# DAPLinkTiny.net
KiCad netlist of a schematic drawn in Altium Designer
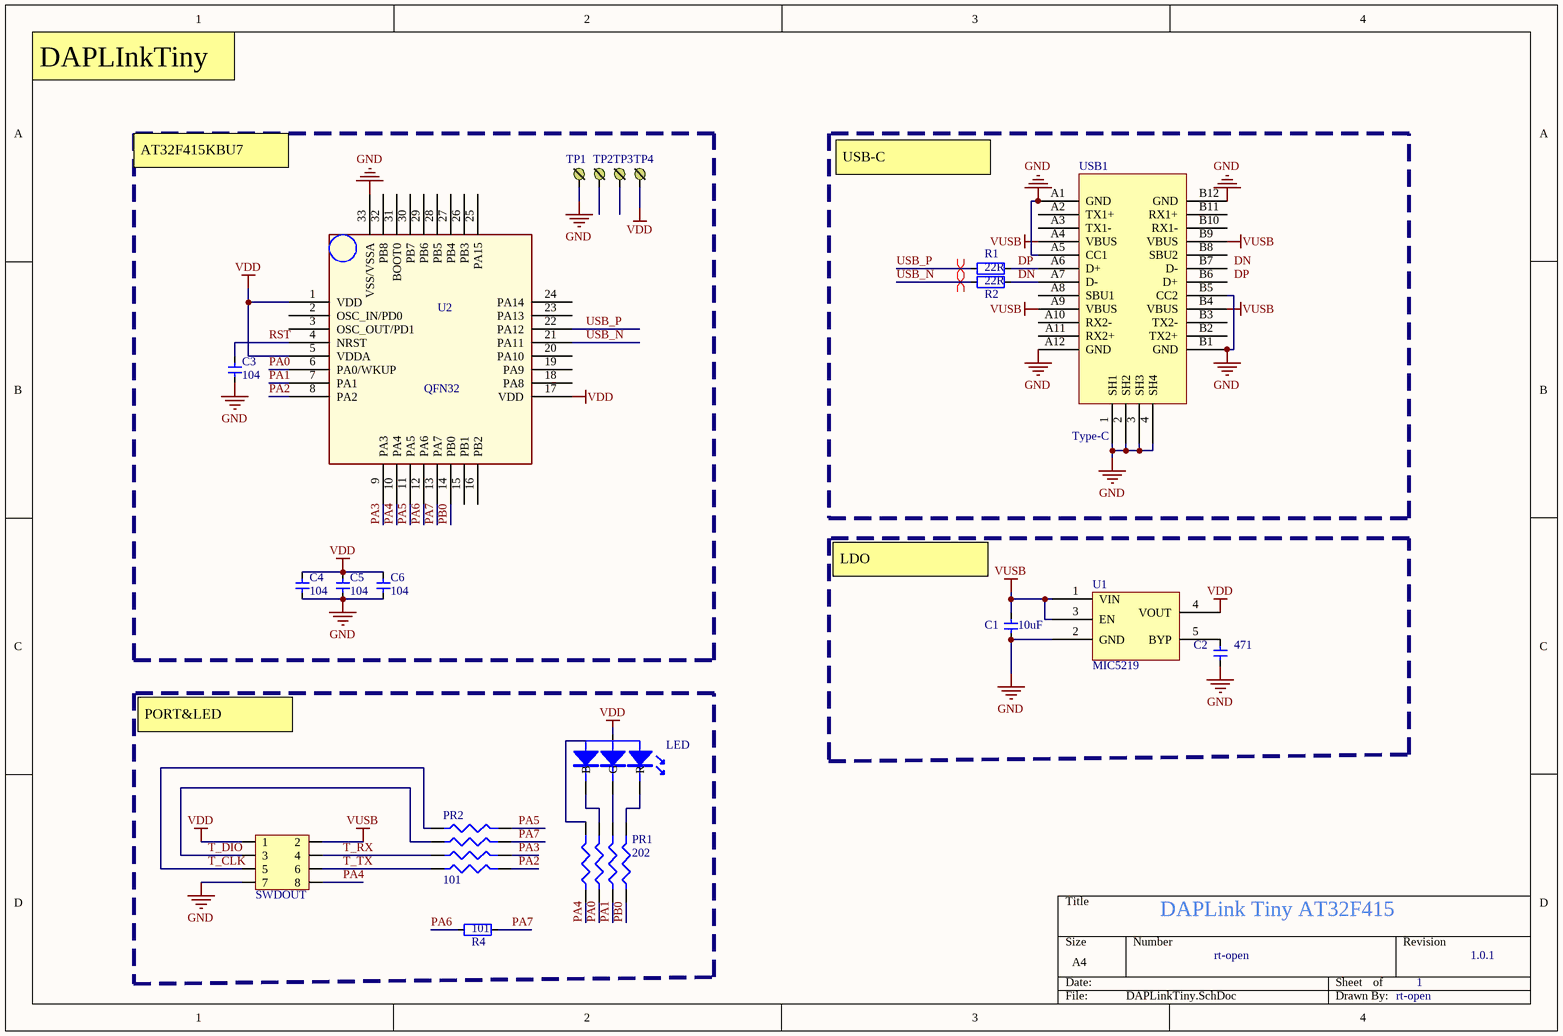
[diagram p0: DAPLinkTiny.SchDoc]

(export (version "E")
  (design (tool "Eeschema 10.0.6"))
  (components
    (comp (ref "C1")
      (value "10uF")
      (footprint "PCB_PassiveCap:CAP_0603")
      (fields (field (name "Comment") "Cap_0603"))
      (libsource (lib "SCH_Passive") (part "Cap_0603"))
    )
    (comp (ref "C2")
      (value "471")
      (footprint "PCB_PassiveCap:CAP_0603")
      (description "Capacitor")
      (fields (field (name "Comment") "Cap_0603"))
      (libsource (lib "SCH_Passive") (part "Cap_0603"))
    )
    (comp (ref "C3")
      (value "104")
      (footprint "PCB_PassiveCap:CAP_0603")
      (description "Capacitor")
      (fields (field (name "Comment") "Cap_0603"))
      (libsource (lib "SCH_Passive") (part "Cap_0603"))
    )
    (comp (ref "C4")
      (value "104")
      (footprint "PCB_PassiveCap:CAP_0603")
      (description "Capacitor")
      (fields (field (name "Comment") "Cap_0603"))
      (libsource (lib "SCH_Passive") (part "Cap_0603"))
    )
    (comp (ref "C5")
      (value "104")
      (footprint "PCB_PassiveCap:CAP_0603")
      (description "Capacitor")
      (fields (field (name "Comment") "Cap_0603"))
      (libsource (lib "SCH_Passive") (part "Cap_0603"))
    )
    (comp (ref "C6")
      (value "104")
      (footprint "PCB_PassiveCap:CAP_0603")
      (description "Capacitor")
      (fields (field (name "Comment") "Cap_0603"))
      (libsource (lib "SCH_Passive") (part "Cap_0603"))
    )
    (comp (ref "LED")
      (value "LTST-C19HE1WT")
      (footprint "LTST-C19HE1WT")
      (libsource (lib "PIXRACER-R12") (part "RGB_LED_5MM"))
    )
    (comp (ref "PR1") (value "202") (footprint "RES4B") (libsource (lib "3DGeneral") (part "RES4B")))
    (comp (ref "PR2") (value "101") (footprint "RES4B") (libsource (lib "3DGeneral") (part "RES4B")))
    (comp (ref "R1")
      (value "22R")
      (footprint "PCB_PassiveRes:RES_0603")
      (description "Resistor")
      (fields (field (name "Comment") "Res_0603"))
      (libsource (lib "SCH_Passive") (part "Res_0603"))
    )
    (comp (ref "R2")
      (value "22R")
      (footprint "PCB_PassiveRes:RES_0603")
      (description "Resistor")
      (fields (field (name "Comment") "Res_0603"))
      (libsource (lib "SCH_Passive") (part "Res_0603"))
    )
    (comp (ref "R4")
      (value "101")
      (footprint "PCB_PassiveRes:RES_0603")
      (description "Resistor")
      (fields (field (name "Comment") "Res_0603"))
      (libsource (lib "SCH_Passive") (part "Res_0603"))
    )
    (comp (ref "SWDOUT")
      (value "HDR2x4_2.54")
      (footprint "PCB_ConnectorHDR:HDR2X4_2.54_180H")
      (description "Header")
      (libsource (lib "SCH_ConnectorHDR") (part "HDR2x4_2.54"))
    )
    (comp (ref "TP1") (value "PLUG") (footprint "SMT_PAD_ROUND") (libsource (lib "AUAV-X1_R1") (part "PLUG")))
    (comp (ref "TP2") (value "PLUG") (footprint "SMT_PAD_ROUND") (libsource (lib "AUAV-X1_R1") (part "PLUG")))
    (comp (ref "TP3") (value "PLUG") (footprint "SMT_PAD_ROUND") (libsource (lib "AUAV-X1_R1") (part "PLUG")))
    (comp (ref "TP4") (value "PLUG") (footprint "SMT_PAD_ROUND") (libsource (lib "AUAV-X1_R1") (part "PLUG")))
    (comp (ref "U1") (value "MIC5219") (footprint "SOT23-5") (libsource (lib "PCB") (part "MIC5219")))
    (comp (ref "U2") (value "QFN32") (libsource (lib "AT32F415-ALL") (part "QFN32")))
    (comp (ref "USB1") (value "Type-C") (footprint "Type-C") (libsource (lib "元件") (part "Type-C")))
  )
  (nets
    (net (code "1") (name "/DN") (class "Default")
      (node (ref "R2") (pin "2") (pinfunction "2_2") (pintype "passive"))
      (node (ref "USB1") (pin "A7") (pinfunction "D-_A7") (pintype "passive"))
    )
    (net (code "2") (name "/DP") (class "Default")
      (node (ref "R1") (pin "2") (pinfunction "2_2") (pintype "passive"))
      (node (ref "USB1") (pin "A6") (pinfunction "D+_A6") (pintype "passive"))
    )
    (net (code "3") (name "/PA0") (class "Default")
      (node (ref "PR1") (pin "3") (pinfunction "R2_3") (pintype "passive"))
      (node (ref "U2") (pin "6") (pinfunction "PA0/WKUP_6") (pintype "passive"))
    )
    (net (code "4") (name "/PA1") (class "Default")
      (node (ref "PR1") (pin "5") (pinfunction "R3_5") (pintype "passive"))
      (node (ref "U2") (pin "7") (pinfunction "PA1_7") (pintype "passive"))
    )
    (net (code "5") (name "/PA2") (class "Default")
      (node (ref "PR2") (pin "8") (pinfunction "R0_8") (pintype "passive"))
      (node (ref "U2") (pin "8") (pinfunction "PA2_8") (pintype "passive"))
    )
    (net (code "6") (name "/PA3") (class "Default")
      (node (ref "PR2") (pin "6") (pinfunction "R2_6") (pintype "passive"))
      (node (ref "U2") (pin "9") (pinfunction "PA3_9") (pintype "passive"))
    )
    (net (code "7") (name "/PA4") (class "Default")
      (node (ref "PR1") (pin "1") (pinfunction "R0_1") (pintype "passive"))
      (node (ref "SWDOUT") (pin "8") (pinfunction "8_8") (pintype "passive"))
      (node (ref "U2") (pin "10") (pinfunction "PA4_10") (pintype "passive"))
    )
    (net (code "8") (name "/PA5") (class "Default")
      (node (ref "PR2") (pin "2") (pinfunction "R1_2") (pintype "passive"))
      (node (ref "U2") (pin "11") (pinfunction "PA5_11") (pintype "passive"))
    )
    (net (code "9") (name "/PA6") (class "Default")
      (node (ref "R4") (pin "1") (pinfunction "1_1") (pintype "passive"))
      (node (ref "U2") (pin "12") (pinfunction "PA6_12") (pintype "passive"))
    )
    (net (code "10") (name "/PA7") (class "Default")
      (node (ref "PR2") (pin "4") (pinfunction "R3_4") (pintype "passive"))
      (node (ref "R4") (pin "2") (pinfunction "2_2") (pintype "passive"))
      (node (ref "U2") (pin "13") (pinfunction "PA7_13") (pintype "passive"))
    )
    (net (code "11") (name "/PB0") (class "Default")
      (node (ref "PR1") (pin "7") (pinfunction "R1_7") (pintype "passive"))
      (node (ref "U2") (pin "14") (pinfunction "PB0_14") (pintype "passive"))
    )
    (net (code "12") (name "/RST") (class "Default")
      (node (ref "C3") (pin "2") (pinfunction "2_2") (pintype "passive"))
      (node (ref "U2") (pin "4") (pinfunction "NRST_4") (pintype "passive"))
    )
    (net (code "13") (name "/T_CLK") (class "Default")
      (node (ref "PR2") (pin "1") (pinfunction "R0_1") (pintype "passive"))
      (node (ref "SWDOUT") (pin "5") (pinfunction "5_5") (pintype "passive"))
    )
    (net (code "14") (name "/T_DIO") (class "Default")
      (node (ref "PR2") (pin "3") (pinfunction "R2_3") (pintype "passive"))
      (node (ref "SWDOUT") (pin "3") (pinfunction "3_3") (pintype "passive"))
    )
    (net (code "15") (name "/T_RX") (class "Default")
      (node (ref "PR2") (pin "5") (pinfunction "R3_5") (pintype "passive"))
      (node (ref "SWDOUT") (pin "4") (pinfunction "4_4") (pintype "passive"))
    )
    (net (code "16") (name "/T_TX") (class "Default")
      (node (ref "PR2") (pin "7") (pinfunction "R1_7") (pintype "passive"))
      (node (ref "SWDOUT") (pin "6") (pinfunction "6_6") (pintype "passive"))
    )
    (net (code "17") (name "/USB_N") (class "Default")
      (node (ref "R2") (pin "1") (pinfunction "1_1") (pintype "passive"))
      (node (ref "U2") (pin "21") (pinfunction "PA11_21") (pintype "passive"))
    )
    (net (code "18") (name "/USB_P") (class "Default")
      (node (ref "R1") (pin "1") (pinfunction "1_1") (pintype "passive"))
      (node (ref "U2") (pin "22") (pinfunction "PA12_22") (pintype "passive"))
    )
    (net (code "19") (name "GND") (class "Default")
      (node (ref "C1") (pin "1") (pinfunction "1_1") (pintype "passive"))
      (node (ref "C2") (pin "1") (pinfunction "1_1") (pintype "passive"))
      (node (ref "C3") (pin "1") (pinfunction "1_1") (pintype "passive"))
      (node (ref "C4") (pin "1") (pinfunction "1_1") (pintype "passive"))
      (node (ref "C5") (pin "1") (pinfunction "1_1") (pintype "passive"))
      (node (ref "C6") (pin "1") (pinfunction "1_1") (pintype "passive"))
      (node (ref "SWDOUT") (pin "7") (pinfunction "7_7") (pintype "passive"))
      (node (ref "TP1") (pin "1") (pintype "passive"))
      (node (ref "U1") (pin "2") (pinfunction "GND_2") (pintype "passive"))
      (node (ref "U2") (pin "33") (pinfunction "VSS/VSSA_33") (pintype "passive"))
      (node (ref "USB1") (pin "1") (pinfunction "SH1_1") (pintype "passive"))
      (node (ref "USB1") (pin "2") (pinfunction "SH2_2") (pintype "passive"))
      (node (ref "USB1") (pin "3") (pinfunction "SH3_3") (pintype "passive"))
      (node (ref "USB1") (pin "4") (pinfunction "SH4_4") (pintype "passive"))
      (node (ref "USB1") (pin "A1") (pinfunction "GND_A1") (pintype "passive"))
      (node (ref "USB1") (pin "A12") (pinfunction "GND_A12") (pintype "passive"))
      (node (ref "USB1") (pin "A5") (pinfunction "CC1_A5") (pintype "passive"))
      (node (ref "USB1") (pin "B1") (pinfunction "GND_B1") (pintype "passive"))
      (node (ref "USB1") (pin "B12") (pinfunction "GND_B12") (pintype "passive"))
      (node (ref "USB1") (pin "B5") (pinfunction "CC2_B5") (pintype "passive"))
    )
    (net (code "20") (name "Net-(LED-B)") (class "Default")
      (node (ref "LED") (pin "3") (pinfunction "B_3") (pintype "passive"))
      (node (ref "PR1") (pin "4") (pinfunction "R3_4") (pintype "passive"))
    )
    (net (code "21") (name "Net-(LED-G)") (class "Default")
      (node (ref "LED") (pin "2") (pinfunction "G_2") (pintype "passive"))
      (node (ref "PR1") (pin "6") (pinfunction "R2_6") (pintype "passive"))
    )
    (net (code "22") (name "Net-(LED-R)") (class "Default")
      (node (ref "LED") (pin "1") (pinfunction "R_1") (pintype "passive"))
      (node (ref "PR1") (pin "8") (pinfunction "R0_8") (pintype "passive"))
    )
    (net (code "23") (name "Net-(U1-BYP)") (class "Default")
      (node (ref "C2") (pin "2") (pinfunction "2_2") (pintype "passive"))
      (node (ref "U1") (pin "5") (pinfunction "BYP_5") (pintype "passive"))
    )
    (net (code "24") (name "VDD") (class "Default")
      (node (ref "C4") (pin "2") (pinfunction "2_2") (pintype "passive"))
      (node (ref "C5") (pin "2") (pinfunction "2_2") (pintype "passive"))
      (node (ref "C6") (pin "2") (pinfunction "2_2") (pintype "passive"))
      (node (ref "LED") (pin "4") (pinfunction "A_4") (pintype "passive"))
      (node (ref "SWDOUT") (pin "1") (pinfunction "1_1") (pintype "passive"))
      (node (ref "TP4") (pin "1") (pintype "passive"))
      (node (ref "U1") (pin "4") (pinfunction "VOUT_4") (pintype "passive"))
      (node (ref "U2") (pin "1") (pinfunction "VDD_1") (pintype "passive"))
      (node (ref "U2") (pin "17") (pinfunction "VDD_17") (pintype "passive"))
      (node (ref "U2") (pin "5") (pinfunction "VDDA_5") (pintype "passive"))
    )
    (net (code "25") (name "VUSB") (class "Default")
      (node (ref "C1") (pin "2") (pinfunction "2_2") (pintype "passive"))
      (node (ref "SWDOUT") (pin "2") (pinfunction "2_2") (pintype "passive"))
      (node (ref "U1") (pin "1") (pinfunction "VIN_1") (pintype "passive"))
      (node (ref "U1") (pin "3") (pinfunction "EN_3") (pintype "passive"))
      (node (ref "USB1") (pin "A4") (pinfunction "VBUS_A4") (pintype "passive"))
      (node (ref "USB1") (pin "A9") (pinfunction "VBUS_A9") (pintype "passive"))
      (node (ref "USB1") (pin "B4") (pinfunction "VBUS_B4") (pintype "passive"))
      (node (ref "USB1") (pin "B9") (pinfunction "VBUS_B9") (pintype "passive"))
    )
    (net (code "26") (name "unconnected-(PR1-R1-Pad2)") (class "Default")
      (node (ref "PR1") (pin "2") (pinfunction "R1_2") (pintype "passive"))
    )
    (net (code "27") (name "unconnected-(TP2-Pad1)") (class "Default")
      (node (ref "TP2") (pin "1") (pintype "passive"))
    )
    (net (code "28") (name "unconnected-(TP3-Pad1)") (class "Default")
      (node (ref "TP3") (pin "1") (pintype "passive"))
    )
    (net (code "29") (name "unconnected-(U2-BOOT0-Pad31)") (class "Default")
      (node (ref "U2") (pin "31") (pinfunction "BOOT0_31") (pintype "passive"))
    )
    (net (code "30") (name "unconnected-(U2-OSC_IN{slash}PD0-Pad2)") (class "Default")
      (node (ref "U2") (pin "2") (pinfunction "OSC_IN/PD0_2") (pintype "passive"))
    )
    (net (code "31") (name "unconnected-(U2-OSC_OUT{slash}PD1-Pad3)") (class "Default")
      (node (ref "U2") (pin "3") (pinfunction "OSC_OUT/PD1_3") (pintype "passive"))
    )
    (net (code "32") (name "unconnected-(U2-PA8-Pad18)") (class "Default")
      (node (ref "U2") (pin "18") (pinfunction "PA8_18") (pintype "passive"))
    )
    (net (code "33") (name "unconnected-(U2-PA9-Pad19)") (class "Default")
      (node (ref "U2") (pin "19") (pinfunction "PA9_19") (pintype "passive"))
    )
    (net (code "34") (name "unconnected-(U2-PA10-Pad20)") (class "Default")
      (node (ref "U2") (pin "20") (pinfunction "PA10_20") (pintype "passive"))
    )
    (net (code "35") (name "unconnected-(U2-PA13-Pad23)") (class "Default")
      (node (ref "U2") (pin "23") (pinfunction "PA13_23") (pintype "passive"))
    )
    (net (code "36") (name "unconnected-(U2-PA14-Pad24)") (class "Default")
      (node (ref "U2") (pin "24") (pinfunction "PA14_24") (pintype "passive"))
    )
    (net (code "37") (name "unconnected-(U2-PA15-Pad25)") (class "Default")
      (node (ref "U2") (pin "25") (pinfunction "PA15_25") (pintype "passive"))
    )
    (net (code "38") (name "unconnected-(U2-PB1-Pad15)") (class "Default")
      (node (ref "U2") (pin "15") (pinfunction "PB1_15") (pintype "passive"))
    )
    (net (code "39") (name "unconnected-(U2-PB2-Pad16)") (class "Default")
      (node (ref "U2") (pin "16") (pinfunction "PB2_16") (pintype "passive"))
    )
    (net (code "40") (name "unconnected-(U2-PB3-Pad26)") (class "Default")
      (node (ref "U2") (pin "26") (pinfunction "PB3_26") (pintype "passive"))
    )
    (net (code "41") (name "unconnected-(U2-PB4-Pad27)") (class "Default")
      (node (ref "U2") (pin "27") (pinfunction "PB4_27") (pintype "passive"))
    )
    (net (code "42") (name "unconnected-(U2-PB5-Pad28)") (class "Default")
      (node (ref "U2") (pin "28") (pinfunction "PB5_28") (pintype "passive"))
    )
    (net (code "43") (name "unconnected-(U2-PB6-Pad29)") (class "Default")
      (node (ref "U2") (pin "29") (pinfunction "PB6_29") (pintype "passive"))
    )
    (net (code "44") (name "unconnected-(U2-PB7-Pad30)") (class "Default")
      (node (ref "U2") (pin "30") (pinfunction "PB7_30") (pintype "passive"))
    )
    (net (code "45") (name "unconnected-(U2-PB8-Pad32)") (class "Default")
      (node (ref "U2") (pin "32") (pinfunction "PB8_32") (pintype "passive"))
    )
    (net (code "46") (name "unconnected-(USB1-D+-PadB6)") (class "Default")
      (node (ref "USB1") (pin "B6") (pinfunction "D+_B6") (pintype "passive"))
    )
    (net (code "47") (name "unconnected-(USB1-D--PadB7)") (class "Default")
      (node (ref "USB1") (pin "B7") (pinfunction "D-_B7") (pintype "passive"))
    )
    (net (code "48") (name "unconnected-(USB1-RX1+-PadB11)") (class "Default")
      (node (ref "USB1") (pin "B11") (pinfunction "RX1+_B11") (pintype "passive"))
    )
    (net (code "49") (name "unconnected-(USB1-RX1--PadB10)") (class "Default")
      (node (ref "USB1") (pin "B10") (pinfunction "RX1-_B10") (pintype "passive"))
    )
    (net (code "50") (name "unconnected-(USB1-RX2+-PadA11)") (class "Default")
      (node (ref "USB1") (pin "A11") (pinfunction "RX2+_A11") (pintype "passive"))
    )
    (net (code "51") (name "unconnected-(USB1-RX2--PadA10)") (class "Default")
      (node (ref "USB1") (pin "A10") (pinfunction "RX2-_A10") (pintype "passive"))
    )
    (net (code "52") (name "unconnected-(USB1-SBU1-PadA8)") (class "Default")
      (node (ref "USB1") (pin "A8") (pinfunction "SBU1_A8") (pintype "passive"))
    )
    (net (code "53") (name "unconnected-(USB1-SBU2-PadB8)") (class "Default")
      (node (ref "USB1") (pin "B8") (pinfunction "SBU2_B8") (pintype "passive"))
    )
    (net (code "54") (name "unconnected-(USB1-TX1+-PadA2)") (class "Default")
      (node (ref "USB1") (pin "A2") (pinfunction "TX1+_A2") (pintype "passive"))
    )
    (net (code "55") (name "unconnected-(USB1-TX1--PadA3)") (class "Default")
      (node (ref "USB1") (pin "A3") (pinfunction "TX1-_A3") (pintype "passive"))
    )
    (net (code "56") (name "unconnected-(USB1-TX2+-PadB2)") (class "Default")
      (node (ref "USB1") (pin "B2") (pinfunction "TX2+_B2") (pintype "passive"))
    )
    (net (code "57") (name "unconnected-(USB1-TX2--PadB3)") (class "Default")
      (node (ref "USB1") (pin "B3") (pinfunction "TX2-_B3") (pintype "passive"))
    )
  )
)
